# KSS_4_info_LED.net
KiCad netlist of a schematic drawn in Altium Designer
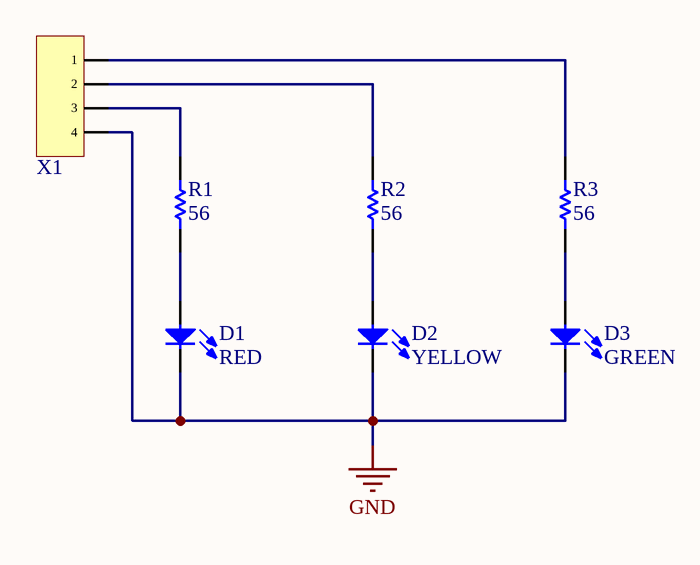
[diagram p0: KSS_4_info_LED.SchDoc]

(export (version "E")
  (design (tool "Eeschema 10.0.6"))
  (components
    (comp (ref "D1")
      (value "RED")
      (footprint "LED_RED_3mm")
      (libsource (lib "COMPONENTS_2022") (part "Diode LED"))
    )
    (comp (ref "D2")
      (value "YELLOW")
      (footprint "LED_YELLOW_3mm")
      (libsource (lib "COMPONENTS_2022") (part "Diode LED"))
    )
    (comp (ref "D3")
      (value "GREEN")
      (footprint "LED_GREEN_3mm")
      (libsource (lib "COMPONENTS_2022") (part "Diode LED"))
    )
    (comp (ref "R1")
      (value "Resistor")
      (footprint "RES_0603")
      (fields (field (name "RESISTANCE") "56"))
      (libsource (lib "COMPONENTS_2022") (part "Resistor"))
    )
    (comp (ref "R2")
      (value "Resistor")
      (footprint "RES_0603")
      (fields (field (name "RESISTANCE") "56"))
      (libsource (lib "COMPONENTS_2022") (part "Resistor"))
    )
    (comp (ref "R3")
      (value "Resistor")
      (footprint "RES_0603")
      (fields (field (name "RESISTANCE") "56"))
      (libsource (lib "COMPONENTS_2022") (part "Resistor"))
    )
    (comp (ref "X1")
      (value "HEADER_X4")
      (footprint "HEADER_1X4_M")
      (libsource (lib "HEADERS") (part "HEADER_X4"))
    )
  )
  (nets
    (net (code "1") (name "GND") (class "Default")
      (node (ref "D1") (pin "2") (pinfunction "K_2") (pintype "passive"))
      (node (ref "D2") (pin "2") (pinfunction "K_2") (pintype "passive"))
      (node (ref "D3") (pin "2") (pinfunction "K_2") (pintype "passive"))
      (node (ref "X1") (pin "4") (pinfunction "4_4") (pintype "passive"))
    )
    (net (code "2") (name "Net-(D1-A)") (class "Default")
      (node (ref "D1") (pin "1") (pinfunction "A_1") (pintype "passive"))
      (node (ref "R1") (pin "1") (pinfunction "1_1") (pintype "passive"))
    )
    (net (code "3") (name "Net-(D2-A)") (class "Default")
      (node (ref "D2") (pin "1") (pinfunction "A_1") (pintype "passive"))
      (node (ref "R2") (pin "1") (pinfunction "1_1") (pintype "passive"))
    )
    (net (code "4") (name "Net-(D3-A)") (class "Default")
      (node (ref "D3") (pin "1") (pinfunction "A_1") (pintype "passive"))
      (node (ref "R3") (pin "1") (pinfunction "1_1") (pintype "passive"))
    )
    (net (code "5") (name "Net-(R1-Pad2)") (class "Default")
      (node (ref "R1") (pin "2") (pinfunction "2_2") (pintype "passive"))
      (node (ref "X1") (pin "3") (pinfunction "3_3") (pintype "passive"))
    )
    (net (code "6") (name "Net-(R2-Pad2)") (class "Default")
      (node (ref "R2") (pin "2") (pinfunction "2_2") (pintype "passive"))
      (node (ref "X1") (pin "2") (pinfunction "2_2") (pintype "passive"))
    )
    (net (code "7") (name "Net-(R3-Pad2)") (class "Default")
      (node (ref "R3") (pin "2") (pinfunction "2_2") (pintype "passive"))
      (node (ref "X1") (pin "1") (pinfunction "1_1") (pintype "passive"))
    )
  )
)
